# Spectron2.net
KiCad netlist of a schematic drawn in EAGLE
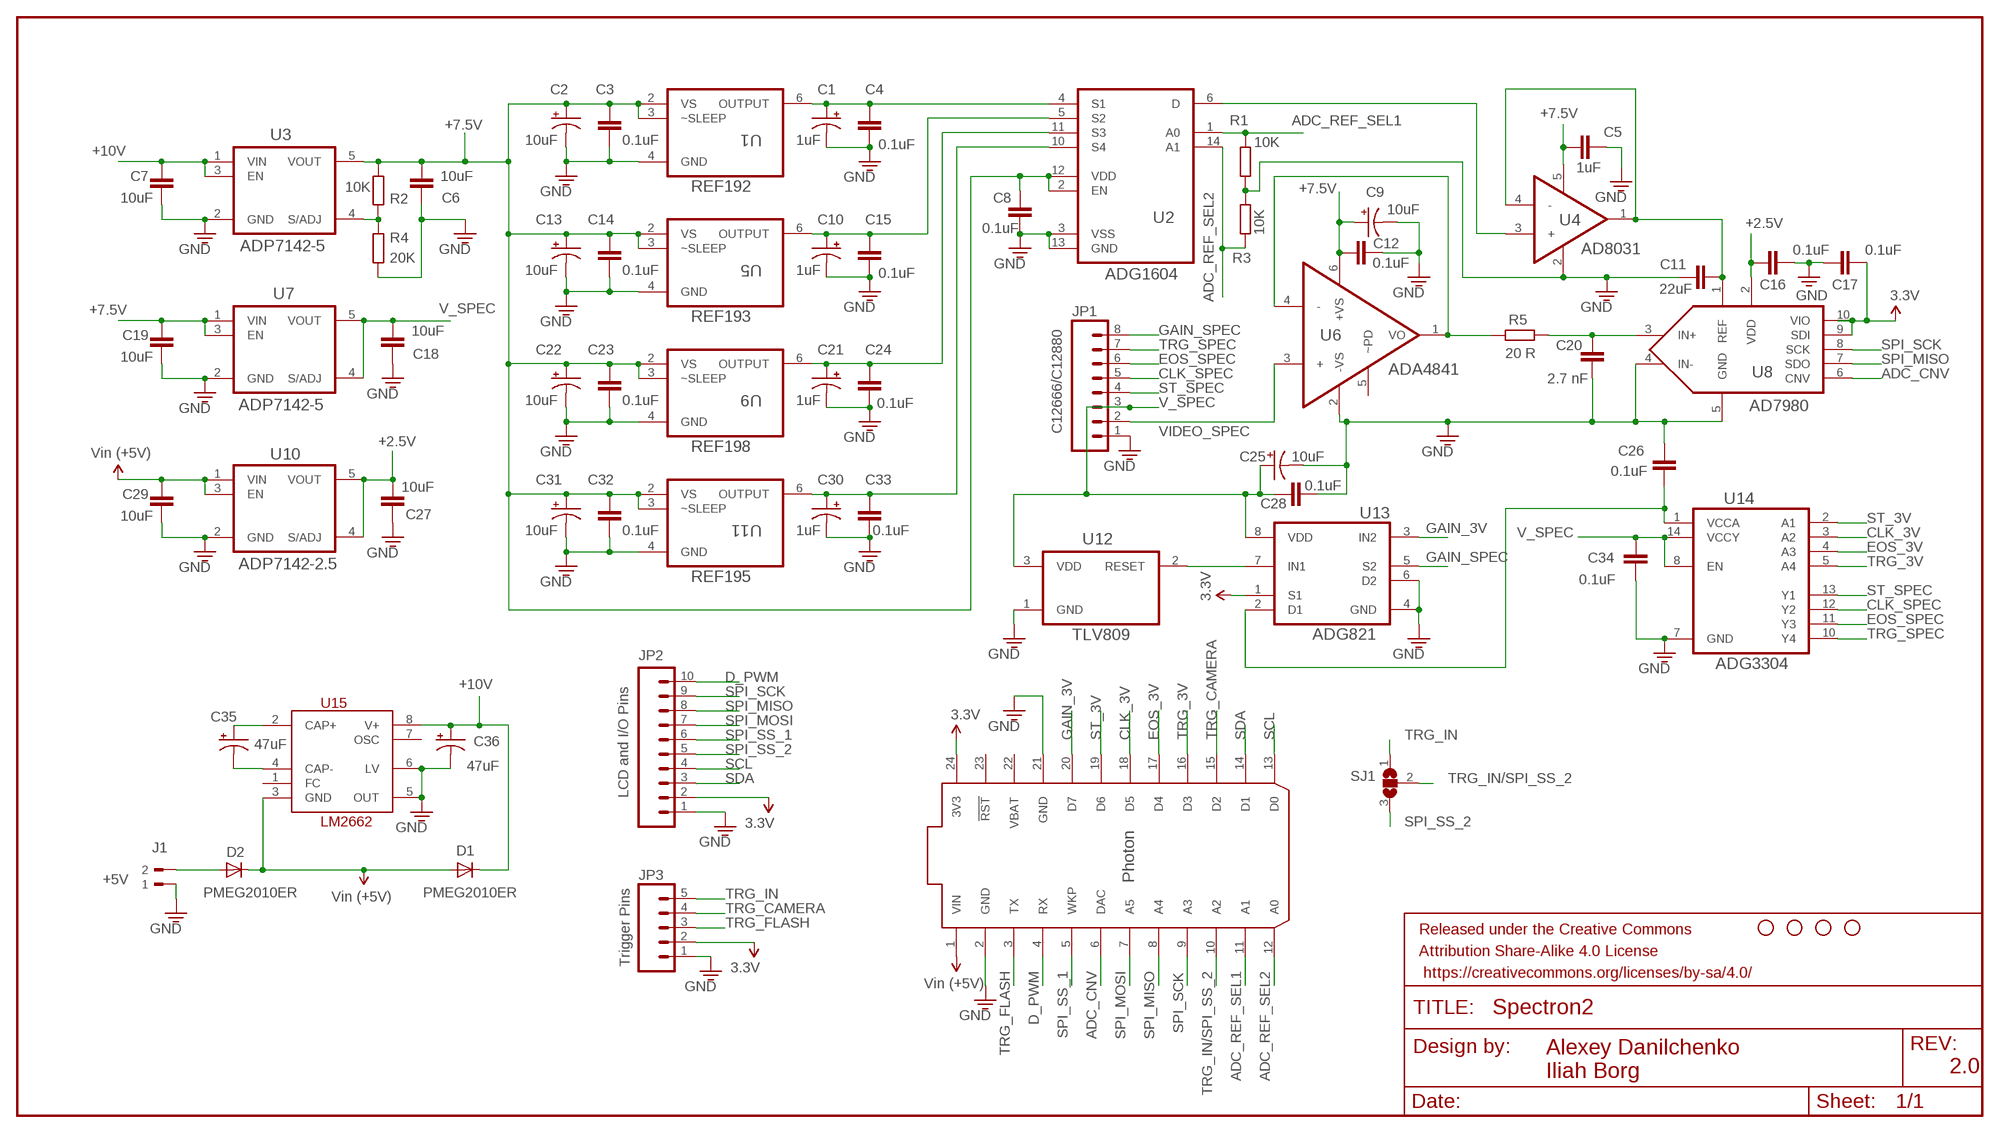
[diagram p0: schematic, sheet 1]

(export (version "E")
  (design (tool "Eeschema 10.0.6"))
  (components
    (comp (ref "C1")
      (value "1uF")
      (footprint "eagle-import:EIA3216")
      (libsource (lib "eagle-import") (part "TANT-CAP1206"))
    )
    (comp (ref "C2")
      (value "10uF")
      (footprint "eagle-import:EIA3216")
      (libsource (lib "eagle-import") (part "Spectron2_TANT-CAP1206"))
    )
    (comp (ref "C3")
      (value "0.1uF")
      (footprint "eagle-import:C0805")
      (libsource (lib "eagle-import") (part "C-EUC0805"))
    )
    (comp (ref "C4")
      (value "0.1uF")
      (footprint "eagle-import:C0805")
      (libsource (lib "eagle-import") (part "C-EUC0805"))
    )
    (comp (ref "C5")
      (value "1uF")
      (footprint "eagle-import:C0805")
      (libsource (lib "eagle-import") (part "C-EUC0805"))
    )
    (comp (ref "C6")
      (value "10uF")
      (footprint "eagle-import:C0805")
      (libsource (lib "eagle-import") (part "C-EUC0805"))
    )
    (comp (ref "C7")
      (value "10uF")
      (footprint "eagle-import:C0805")
      (libsource (lib "eagle-import") (part "C-EUC0805"))
    )
    (comp (ref "C8")
      (value "0.1uF")
      (footprint "eagle-import:C0805")
      (libsource (lib "eagle-import") (part "C-EUC0805"))
    )
    (comp (ref "C9")
      (value "10uF")
      (footprint "eagle-import:EIA3216")
      (libsource (lib "eagle-import") (part "Spectron2_TANT-CAP1206"))
    )
    (comp (ref "C10")
      (value "1uF")
      (footprint "eagle-import:EIA3216")
      (libsource (lib "eagle-import") (part "TANT-CAP1206"))
    )
    (comp (ref "C11")
      (value "22uF")
      (footprint "eagle-import:1206")
      (libsource (lib "eagle-import") (part "CAP1206"))
    )
    (comp (ref "C12")
      (value "0.1uF")
      (footprint "eagle-import:C0805")
      (libsource (lib "eagle-import") (part "C-EUC0805"))
    )
    (comp (ref "C13")
      (value "10uF")
      (footprint "eagle-import:EIA3216")
      (libsource (lib "eagle-import") (part "Spectron2_TANT-CAP1206"))
    )
    (comp (ref "C14")
      (value "0.1uF")
      (footprint "eagle-import:C0805")
      (libsource (lib "eagle-import") (part "C-EUC0805"))
    )
    (comp (ref "C15")
      (value "0.1uF")
      (footprint "eagle-import:C0805")
      (libsource (lib "eagle-import") (part "C-EUC0805"))
    )
    (comp (ref "C16")
      (value "0.1uF")
      (footprint "eagle-import:C0805")
      (libsource (lib "eagle-import") (part "C-EUC0805"))
    )
    (comp (ref "C17")
      (value "0.1uF")
      (footprint "eagle-import:C0805")
      (libsource (lib "eagle-import") (part "C-EUC0805"))
    )
    (comp (ref "C18")
      (value "10uF")
      (footprint "eagle-import:C0805")
      (libsource (lib "eagle-import") (part "C-EUC0805"))
    )
    (comp (ref "C19")
      (value "10uF")
      (footprint "eagle-import:C0805")
      (libsource (lib "eagle-import") (part "C-EUC0805"))
    )
    (comp (ref "C20")
      (value "2.7 nF")
      (footprint "eagle-import:C0805")
      (libsource (lib "eagle-import") (part "C-EUC0805"))
    )
    (comp (ref "C21")
      (value "1uF")
      (footprint "eagle-import:EIA3216")
      (libsource (lib "eagle-import") (part "TANT-CAP1206"))
    )
    (comp (ref "C22")
      (value "10uF")
      (footprint "eagle-import:EIA3216")
      (libsource (lib "eagle-import") (part "Spectron2_TANT-CAP1206"))
    )
    (comp (ref "C23")
      (value "0.1uF")
      (footprint "eagle-import:C0805")
      (libsource (lib "eagle-import") (part "C-EUC0805"))
    )
    (comp (ref "C24")
      (value "0.1uF")
      (footprint "eagle-import:C0805")
      (libsource (lib "eagle-import") (part "C-EUC0805"))
    )
    (comp (ref "C25")
      (value "10uF")
      (footprint "eagle-import:EIA3216")
      (libsource (lib "eagle-import") (part "Spectron2_TANT-CAP1206"))
    )
    (comp (ref "C26")
      (value "0.1uF")
      (footprint "eagle-import:C0805")
      (libsource (lib "eagle-import") (part "C-EUC0805"))
    )
    (comp (ref "C27")
      (value "10uF")
      (footprint "eagle-import:C0805")
      (libsource (lib "eagle-import") (part "C-EUC0805"))
    )
    (comp (ref "C28")
      (value "0.1uF")
      (footprint "eagle-import:C0805")
      (libsource (lib "eagle-import") (part "C-EUC0805"))
    )
    (comp (ref "C29")
      (value "10uF")
      (footprint "eagle-import:C0805")
      (libsource (lib "eagle-import") (part "C-EUC0805"))
    )
    (comp (ref "C30")
      (value "1uF")
      (footprint "eagle-import:EIA3216")
      (libsource (lib "eagle-import") (part "TANT-CAP1206"))
    )
    (comp (ref "C31")
      (value "10uF")
      (footprint "eagle-import:EIA3216")
      (libsource (lib "eagle-import") (part "Spectron2_TANT-CAP1206"))
    )
    (comp (ref "C32")
      (value "0.1uF")
      (footprint "eagle-import:C0805")
      (libsource (lib "eagle-import") (part "C-EUC0805"))
    )
    (comp (ref "C33")
      (value "0.1uF")
      (footprint "eagle-import:C0805")
      (libsource (lib "eagle-import") (part "C-EUC0805"))
    )
    (comp (ref "C34")
      (value "0.1uF")
      (footprint "eagle-import:C0805")
      (libsource (lib "eagle-import") (part "C-EUC0805"))
    )
    (comp (ref "C35")
      (value "47uF")
      (footprint "eagle-import:CT7343")
      (libsource (lib "eagle-import") (part "CPOL-USCT7343"))
    )
    (comp (ref "C36")
      (value "47uF")
      (footprint "eagle-import:CT7343")
      (libsource (lib "eagle-import") (part "CPOL-USCT7343"))
    )
    (comp (ref "D1")
      (value "PMEG2010ER")
      (footprint "eagle-import:SOD123")
      (libsource (lib "eagle-import") (part "DIODE-SOD123"))
    )
    (comp (ref "D2")
      (value "PMEG2010ER")
      (footprint "eagle-import:SOD123")
      (libsource (lib "eagle-import") (part "DIODE-SOD123"))
    )
    (comp (ref "FRAME1")
      (value "FRAME-LEDGER")
      (footprint "eagle-import:CREATIVE_COMMONS")
      (libsource (lib "eagle-import") (part "FRAME-LEDGER"))
    )
    (comp (ref "J1")
      (value "+5V")
      (footprint "eagle-import:WEIDMULLER_PM5.08_2")
      (fields (field (name "MPN") "PM5.08/2/90 BLK"))
      (libsource (lib "eagle-import") (part "PM5.08/2/90BLK"))
    )
    (comp (ref "JP1")
      (value "C12666/C12880")
      (footprint "eagle-import:1X08")
      (libsource (lib "eagle-import") (part "M08SILK_FEMALE_PTH"))
    )
    (comp (ref "JP2")
      (value "LCD and I/O Pins")
      (footprint "eagle-import:1X10")
      (libsource (lib "eagle-import") (part "M10SILK_FEMALE_PTH"))
    )
    (comp (ref "JP3")
      (value "Trigger Pins")
      (footprint "eagle-import:1X05")
      (libsource (lib "eagle-import") (part "M05PTH"))
    )
    (comp (ref "R1")
      (value "10K")
      (footprint "eagle-import:R0805")
      (libsource (lib "eagle-import") (part "R-EU_R0805"))
    )
    (comp (ref "R2")
      (value "10K")
      (footprint "eagle-import:R0805")
      (libsource (lib "eagle-import") (part "R-EU_R0805"))
    )
    (comp (ref "R3")
      (value "10K")
      (footprint "eagle-import:R0805")
      (libsource (lib "eagle-import") (part "R-EU_R0805"))
    )
    (comp (ref "R4")
      (value "20K")
      (footprint "eagle-import:R0805")
      (libsource (lib "eagle-import") (part "R-EU_R0805"))
    )
    (comp (ref "R5")
      (value "20 R")
      (footprint "eagle-import:R0805")
      (libsource (lib "eagle-import") (part "R-EU_R0805"))
    )
    (comp (ref "SJ1")
      (value "SJ2W")
      (footprint "eagle-import:SJ_2")
      (libsource (lib "eagle-import") (part "SJ2W"))
    )
    (comp (ref "STANDOFF1")
      (value "STAND-OFF")
      (footprint "eagle-import:STAND-OFF")
      (libsource (lib "eagle-import") (part "STAND-OFF"))
    )
    (comp (ref "STANDOFF2")
      (value "STAND-OFF")
      (footprint "eagle-import:STAND-OFF")
      (libsource (lib "eagle-import") (part "STAND-OFF"))
    )
    (comp (ref "STANDOFF3")
      (value "STAND-OFF")
      (footprint "eagle-import:STAND-OFF")
      (libsource (lib "eagle-import") (part "STAND-OFF"))
    )
    (comp (ref "STANDOFF4")
      (value "STAND-OFF")
      (footprint "eagle-import:STAND-OFF")
      (libsource (lib "eagle-import") (part "STAND-OFF"))
    )
    (comp (ref "U1")
      (value "REF192")
      (footprint "eagle-import:SOIC127P600X175-8N")
      (libsource (lib "eagle-import") (part "REF192"))
    )
    (comp (ref "U2")
      (value "ADG1604")
      (footprint "eagle-import:SOP65P640X120-14N")
      (fields (field (name "MPN") "ADG1604BRUZ"))
      (libsource (lib "eagle-import") (part "ADG1604"))
    )
    (comp (ref "U3")
      (value "ADP7142-5")
      (footprint "eagle-import:SOT95P280X145-5N")
      (fields (field (name "MPN") "ADP7142"))
      (libsource (lib "eagle-import") (part "ADP7142"))
    )
    (comp (ref "U4")
      (value "AD8031")
      (footprint "eagle-import:SOT95P280X145-5N")
      (libsource (lib "eagle-import") (part "AD8031"))
    )
    (comp (ref "U5")
      (value "REF193")
      (footprint "eagle-import:SOIC127P600X175-8N")
      (libsource (lib "eagle-import") (part "REF193"))
    )
    (comp (ref "U6")
      (value "ADA4841")
      (footprint "eagle-import:SOT95P280X145-6N")
      (fields (field (name "MPN") "ADA4841-1YRJZ-R2"))
      (libsource (lib "eagle-import") (part "ADA4841"))
    )
    (comp (ref "U7")
      (value "ADP7142-5")
      (footprint "eagle-import:SOT95P280X145-5N")
      (fields (field (name "MPN") "ADP7142"))
      (libsource (lib "eagle-import") (part "ADP7142"))
    )
    (comp (ref "U8")
      (value "AD7980")
      (footprint "eagle-import:SOP50P490X110-10N")
      (fields (field (name "MPN") "AD7980ARMZ"))
      (libsource (lib "eagle-import") (part "AD7980"))
    )
    (comp (ref "U9")
      (value "REF198")
      (footprint "eagle-import:SOIC127P600X175-8N")
      (libsource (lib "eagle-import") (part "REF198"))
    )
    (comp (ref "U10")
      (value "ADP7142-2.5")
      (footprint "eagle-import:SOT95P280X145-5N")
      (fields (field (name "MPN") "ADP7142"))
      (libsource (lib "eagle-import") (part "ADP7142"))
    )
    (comp (ref "U11")
      (value "REF195")
      (footprint "eagle-import:SOIC127P600X175-8N")
      (libsource (lib "eagle-import") (part "REF195"))
    )
    (comp (ref "U12")
      (value "TLV809")
      (footprint "eagle-import:SOT95P237X112-3N")
      (fields (field (name "MPN") "TLV80950"))
      (libsource (lib "eagle-import") (part "TLV809"))
    )
    (comp (ref "U13")
      (value "ADG821")
      (footprint "eagle-import:SOP65P490X110-8N")
      (fields (field (name "MPN") "ADG821BRMZ"))
      (libsource (lib "eagle-import") (part "ADG821"))
    )
    (comp (ref "U14")
      (value "ADG3304")
      (footprint "eagle-import:SOP65P640X120-14N")
      (libsource (lib "eagle-import") (part "ADG3304"))
    )
    (comp (ref "U15")
      (value "LM2662")
      (footprint "eagle-import:SOIC8")
      (libsource (lib "eagle-import") (part "LM2662"))
    )
    (comp (ref "U16")
      (value "PHOTON_WITH_HEADERS")
      (footprint "eagle-import:PHOTON")
      (libsource (lib "eagle-import") (part "PHOTON_WITH_HEADERS"))
    )
  )
  (nets
    (net (code "1") (name "/+2.5V") (class "Default")
      (node (ref "C16") (pin "1") (pinfunction "1_1") (pintype "passive"))
      (node (ref "C27") (pin "1") (pinfunction "1_1") (pintype "passive"))
      (node (ref "U10") (pin "4") (pinfunction "S/ADJ_4") (pintype "power_in"))
      (node (ref "U10") (pin "5") (pinfunction "VOUT_5") (pintype "output"))
      (node (ref "U8") (pin "2") (pinfunction "VDD_2") (pintype "power_in"))
    )
    (net (code "2") (name "/+7.5V") (class "Default")
      (node (ref "C12") (pin "2") (pinfunction "2_2") (pintype "passive"))
      (node (ref "C13") (pin "A") (pinfunction "+_A") (pintype "passive"))
      (node (ref "C14") (pin "2") (pinfunction "2_2") (pintype "passive"))
      (node (ref "C19") (pin "2") (pinfunction "2_2") (pintype "passive"))
      (node (ref "C2") (pin "A") (pinfunction "+_A") (pintype "passive"))
      (node (ref "C22") (pin "A") (pinfunction "+_A") (pintype "passive"))
      (node (ref "C23") (pin "2") (pinfunction "2_2") (pintype "passive"))
      (node (ref "C3") (pin "2") (pinfunction "2_2") (pintype "passive"))
      (node (ref "C31") (pin "A") (pinfunction "+_A") (pintype "passive"))
      (node (ref "C32") (pin "2") (pinfunction "2_2") (pintype "passive"))
      (node (ref "C5") (pin "2") (pinfunction "2_2") (pintype "passive"))
      (node (ref "C6") (pin "1") (pinfunction "1_1") (pintype "passive"))
      (node (ref "C8") (pin "2") (pinfunction "2_2") (pintype "passive"))
      (node (ref "C9") (pin "A") (pinfunction "+_A") (pintype "passive"))
      (node (ref "R2") (pin "1") (pinfunction "1_1") (pintype "passive"))
      (node (ref "U1") (pin "2") (pinfunction "VS_2") (pintype "power_in"))
      (node (ref "U1") (pin "3") (pinfunction "~{SLEEP}_3") (pintype "input"))
      (node (ref "U11") (pin "2") (pinfunction "VS_2") (pintype "power_in"))
      (node (ref "U11") (pin "3") (pinfunction "~{SLEEP}_3") (pintype "input"))
      (node (ref "U2") (pin "12") (pinfunction "VDD_12") (pintype "power_in"))
      (node (ref "U2") (pin "2") (pinfunction "EN_2") (pintype "input"))
      (node (ref "U3") (pin "5") (pinfunction "VOUT_5") (pintype "output"))
      (node (ref "U4") (pin "5") (pinfunction "+VS_5") (pintype "power_in"))
      (node (ref "U5") (pin "2") (pinfunction "VS_2") (pintype "power_in"))
      (node (ref "U5") (pin "3") (pinfunction "~{SLEEP}_3") (pintype "input"))
      (node (ref "U6") (pin "6") (pinfunction "+VS_6") (pintype "power_in"))
      (node (ref "U7") (pin "1") (pinfunction "VIN_1") (pintype "input"))
      (node (ref "U7") (pin "3") (pinfunction "EN_3") (pintype "power_in"))
      (node (ref "U9") (pin "2") (pinfunction "VS_2") (pintype "power_in"))
      (node (ref "U9") (pin "3") (pinfunction "~{SLEEP}_3") (pintype "input"))
    )
    (net (code "3") (name "/+10V") (class "Default")
      (node (ref "C36") (pin "+") (pinfunction "+_+") (pintype "passive"))
      (node (ref "C7") (pin "2") (pinfunction "2_2") (pintype "passive"))
      (node (ref "D1") (pin "C") (pinfunction "C_C") (pintype "passive"))
      (node (ref "U15") (pin "8") (pinfunction "V+_8") (pintype "bidirectional"))
      (node (ref "U3") (pin "1") (pinfunction "VIN_1") (pintype "input"))
      (node (ref "U3") (pin "3") (pinfunction "EN_3") (pintype "power_in"))
    )
    (net (code "4") (name "/ADC_CNV") (class "Default")
      (node (ref "U16") (pin "6") (pinfunction "DAC_6") (pintype "bidirectional"))
      (node (ref "U8") (pin "6") (pinfunction "CNV_6") (pintype "input"))
    )
    (net (code "5") (name "/ADC_REF_SEL1") (class "Default")
      (node (ref "R1") (pin "1") (pinfunction "1_1") (pintype "passive"))
      (node (ref "U16") (pin "11") (pinfunction "A1_11") (pintype "bidirectional"))
      (node (ref "U2") (pin "1") (pinfunction "A0_1") (pintype "input"))
    )
    (net (code "6") (name "/ADC_REF_SEL2") (class "Default")
      (node (ref "R3") (pin "2") (pinfunction "2_2") (pintype "passive"))
      (node (ref "U16") (pin "12") (pinfunction "A0_12") (pintype "bidirectional"))
      (node (ref "U2") (pin "14") (pinfunction "A1_14") (pintype "input"))
    )
    (net (code "7") (name "/CLK_3V") (class "Default")
      (node (ref "U14") (pin "3") (pinfunction "A2_3") (pintype "bidirectional"))
      (node (ref "U16") (pin "18") (pinfunction "D5_18") (pintype "bidirectional"))
    )
    (net (code "8") (name "/CLK_SPEC") (class "Default")
      (node (ref "JP1") (pin "5") (pinfunction "5_5") (pintype "passive"))
      (node (ref "U14") (pin "12") (pinfunction "Y2_12") (pintype "bidirectional"))
    )
    (net (code "9") (name "/D_PWM") (class "Default")
      (node (ref "JP2") (pin "10") (pinfunction "10_10") (pintype "passive"))
      (node (ref "U16") (pin "4") (pinfunction "RX_4") (pintype "bidirectional"))
    )
    (net (code "10") (name "/EOS_3V") (class "Default")
      (node (ref "U14") (pin "4") (pinfunction "A3_4") (pintype "bidirectional"))
      (node (ref "U16") (pin "17") (pinfunction "D4_17") (pintype "bidirectional"))
    )
    (net (code "11") (name "/EOS_SPEC") (class "Default")
      (node (ref "JP1") (pin "6") (pinfunction "6_6") (pintype "passive"))
      (node (ref "U14") (pin "11") (pinfunction "Y3_11") (pintype "bidirectional"))
    )
    (net (code "12") (name "/GAIN_3V") (class "Default")
      (node (ref "U13") (pin "3") (pinfunction "IN2_3") (pintype "input"))
      (node (ref "U16") (pin "20") (pinfunction "D7_20") (pintype "bidirectional"))
    )
    (net (code "13") (name "/GAIN_SPEC") (class "Default")
      (node (ref "JP1") (pin "8") (pinfunction "8_8") (pintype "passive"))
      (node (ref "U13") (pin "5") (pinfunction "S2_5") (pintype "bidirectional"))
    )
    (net (code "14") (name "/SCL") (class "Default")
      (node (ref "JP2") (pin "4") (pinfunction "4_4") (pintype "passive"))
      (node (ref "U16") (pin "13") (pinfunction "D0_13") (pintype "bidirectional"))
    )
    (net (code "15") (name "/SDA") (class "Default")
      (node (ref "JP2") (pin "3") (pinfunction "3_3") (pintype "passive"))
      (node (ref "U16") (pin "14") (pinfunction "D1_14") (pintype "bidirectional"))
    )
    (net (code "16") (name "/SPI_MISO") (class "Default")
      (node (ref "JP2") (pin "8") (pinfunction "8_8") (pintype "passive"))
      (node (ref "U16") (pin "8") (pinfunction "A4_8") (pintype "bidirectional"))
      (node (ref "U8") (pin "7") (pinfunction "SDO_7") (pintype "output"))
    )
    (net (code "17") (name "/SPI_MOSI") (class "Default")
      (node (ref "JP2") (pin "7") (pinfunction "7_7") (pintype "passive"))
      (node (ref "U16") (pin "7") (pinfunction "A5_7") (pintype "bidirectional"))
    )
    (net (code "18") (name "/SPI_SCK") (class "Default")
      (node (ref "JP2") (pin "9") (pinfunction "9_9") (pintype "passive"))
      (node (ref "U16") (pin "9") (pinfunction "A3_9") (pintype "bidirectional"))
      (node (ref "U8") (pin "8") (pinfunction "SCK_8") (pintype "input"))
    )
    (net (code "19") (name "/SPI_SS_1") (class "Default")
      (node (ref "JP2") (pin "6") (pinfunction "6_6") (pintype "passive"))
      (node (ref "U16") (pin "5") (pinfunction "WKP_5") (pintype "bidirectional"))
    )
    (net (code "20") (name "/SPI_SS_2") (class "Default")
      (node (ref "JP2") (pin "5") (pinfunction "5_5") (pintype "passive"))
      (node (ref "SJ1") (pin "3") (pinfunction "3_3") (pintype "passive"))
    )
    (net (code "21") (name "/ST_3V") (class "Default")
      (node (ref "U14") (pin "2") (pinfunction "A1_2") (pintype "bidirectional"))
      (node (ref "U16") (pin "19") (pinfunction "D6_19") (pintype "bidirectional"))
    )
    (net (code "22") (name "/ST_SPEC") (class "Default")
      (node (ref "JP1") (pin "4") (pinfunction "4_4") (pintype "passive"))
      (node (ref "U14") (pin "13") (pinfunction "Y1_13") (pintype "bidirectional"))
    )
    (net (code "23") (name "/TRG_3V") (class "Default")
      (node (ref "U14") (pin "5") (pinfunction "A4_5") (pintype "bidirectional"))
      (node (ref "U16") (pin "16") (pinfunction "D3_16") (pintype "bidirectional"))
    )
    (net (code "24") (name "/TRG_CAMERA") (class "Default")
      (node (ref "JP3") (pin "4") (pinfunction "4_4") (pintype "passive"))
      (node (ref "U16") (pin "15") (pinfunction "D2_15") (pintype "bidirectional"))
    )
    (net (code "25") (name "/TRG_FLASH") (class "Default")
      (node (ref "JP3") (pin "3") (pinfunction "3_3") (pintype "passive"))
      (node (ref "U16") (pin "3") (pinfunction "TX_3") (pintype "bidirectional"))
    )
    (net (code "26") (name "/TRG_IN") (class "Default")
      (node (ref "JP3") (pin "5") (pinfunction "5_5") (pintype "passive"))
      (node (ref "SJ1") (pin "1") (pinfunction "1_1") (pintype "passive"))
    )
    (net (code "27") (name "/TRG_IN{slash}SPI_SS_2") (class "Default")
      (node (ref "SJ1") (pin "2") (pinfunction "2_2") (pintype "passive"))
      (node (ref "U16") (pin "10") (pinfunction "A2_10") (pintype "bidirectional"))
    )
    (net (code "28") (name "/TRG_SPEC") (class "Default")
      (node (ref "JP1") (pin "7") (pinfunction "7_7") (pintype "passive"))
      (node (ref "U14") (pin "10") (pinfunction "Y4_10") (pintype "bidirectional"))
    )
    (net (code "29") (name "/VBAT") (class "Default")
      (node (ref "U16") (pin "22") (pinfunction "VBAT_22") (pintype "power_in"))
    )
    (net (code "30") (name "/VIDEO_SPEC") (class "Default")
      (node (ref "JP1") (pin "2") (pinfunction "2_2") (pintype "passive"))
      (node (ref "U6") (pin "3") (pinfunction "+_3") (pintype "input"))
    )
    (net (code "31") (name "/V_SPEC") (class "Default")
      (node (ref "C18") (pin "1") (pinfunction "1_1") (pintype "passive"))
      (node (ref "C25") (pin "A") (pinfunction "+_A") (pintype "passive"))
      (node (ref "C28") (pin "2") (pinfunction "2_2") (pintype "passive"))
      (node (ref "C34") (pin "2") (pinfunction "2_2") (pintype "passive"))
      (node (ref "JP1") (pin "3") (pinfunction "3_3") (pintype "passive"))
      (node (ref "U12") (pin "3") (pinfunction "VDD_3") (pintype "power_in"))
      (node (ref "U13") (pin "8") (pinfunction "VDD_8") (pintype "power_in"))
      (node (ref "U14") (pin "14") (pinfunction "VCCY_14") (pintype "power_in"))
      (node (ref "U14") (pin "8") (pinfunction "EN_8") (pintype "input"))
      (node (ref "U7") (pin "4") (pinfunction "S/ADJ_4") (pintype "power_in"))
      (node (ref "U7") (pin "5") (pinfunction "VOUT_5") (pintype "output"))
    )
    (net (code "32") (name "3.3V") (class "Default")
      (node (ref "C17") (pin "2") (pinfunction "2_2") (pintype "passive"))
      (node (ref "JP2") (pin "2") (pinfunction "2_2") (pintype "passive"))
      (node (ref "JP3") (pin "2") (pinfunction "2_2") (pintype "passive"))
      (node (ref "U13") (pin "1") (pinfunction "S1_1") (pintype "bidirectional"))
      (node (ref "U16") (pin "24") (pinfunction "3V3_24") (pintype "power_in"))
      (node (ref "U8") (pin "10") (pinfunction "VIO_10") (pintype "power_in"))
      (node (ref "U8") (pin "9") (pinfunction "SDI_9") (pintype "input"))
    )
    (net (code "33") (name "GND") (class "Default")
      (node (ref "C1") (pin "C") (pinfunction "-_C") (pintype "passive"))
      (node (ref "C10") (pin "C") (pinfunction "-_C") (pintype "passive"))
      (node (ref "C11") (pin "1") (pinfunction "1_1") (pintype "passive"))
      (node (ref "C12") (pin "1") (pinfunction "1_1") (pintype "passive"))
      (node (ref "C13") (pin "C") (pinfunction "-_C") (pintype "passive"))
      (node (ref "C14") (pin "1") (pinfunction "1_1") (pintype "passive"))
      (node (ref "C15") (pin "1") (pinfunction "1_1") (pintype "passive"))
      (node (ref "C16") (pin "2") (pinfunction "2_2") (pintype "passive"))
      (node (ref "C17") (pin "1") (pinfunction "1_1") (pintype "passive"))
      (node (ref "C18") (pin "2") (pinfunction "2_2") (pintype "passive"))
      (node (ref "C19") (pin "1") (pinfunction "1_1") (pintype "passive"))
      (node (ref "C2") (pin "C") (pinfunction "-_C") (pintype "passive"))
      (node (ref "C20") (pin "1") (pinfunction "1_1") (pintype "passive"))
      (node (ref "C21") (pin "C") (pinfunction "-_C") (pintype "passive"))
      (node (ref "C22") (pin "C") (pinfunction "-_C") (pintype "passive"))
      (node (ref "C23") (pin "1") (pinfunction "1_1") (pintype "passive"))
      (node (ref "C24") (pin "1") (pinfunction "1_1") (pintype "passive"))
      (node (ref "C25") (pin "C") (pinfunction "-_C") (pintype "passive"))
      (node (ref "C26") (pin "2") (pinfunction "2_2") (pintype "passive"))
      (node (ref "C27") (pin "2") (pinfunction "2_2") (pintype "passive"))
      (node (ref "C28") (pin "1") (pinfunction "1_1") (pintype "passive"))
      (node (ref "C29") (pin "1") (pinfunction "1_1") (pintype "passive"))
      (node (ref "C3") (pin "1") (pinfunction "1_1") (pintype "passive"))
      (node (ref "C30") (pin "C") (pinfunction "-_C") (pintype "passive"))
      (node (ref "C31") (pin "C") (pinfunction "-_C") (pintype "passive"))
      (node (ref "C32") (pin "1") (pinfunction "1_1") (pintype "passive"))
      (node (ref "C33") (pin "1") (pinfunction "1_1") (pintype "passive"))
      (node (ref "C34") (pin "1") (pinfunction "1_1") (pintype "passive"))
      (node (ref "C36") (pin "-") (pinfunction "-_-") (pintype "passive"))
      (node (ref "C4") (pin "1") (pinfunction "1_1") (pintype "passive"))
      (node (ref "C5") (pin "1") (pinfunction "1_1") (pintype "passive"))
      (node (ref "C6") (pin "2") (pinfunction "2_2") (pintype "passive"))
      (node (ref "C7") (pin "1") (pinfunction "1_1") (pintype "passive"))
      (node (ref "C8") (pin "1") (pinfunction "1_1") (pintype "passive"))
      (node (ref "C9") (pin "C") (pinfunction "-_C") (pintype "passive"))
      (node (ref "J1") (pin "1") (pinfunction "1_1") (pintype "passive"))
      (node (ref "JP1") (pin "1") (pinfunction "1_1") (pintype "passive"))
      (node (ref "JP2") (pin "1") (pinfunction "1_1") (pintype "passive"))
      (node (ref "JP3") (pin "1") (pinfunction "1_1") (pintype "passive"))
      (node (ref "R1") (pin "2") (pinfunction "2_2") (pintype "passive"))
      (node (ref "R3") (pin "1") (pinfunction "1_1") (pintype "passive"))
      (node (ref "R4") (pin "2") (pinfunction "2_2") (pintype "passive"))
      (node (ref "U1") (pin "4") (pinfunction "GND_4") (pintype "passive"))
      (node (ref "U10") (pin "2") (pinfunction "GND_2") (pintype "input"))
      (node (ref "U11") (pin "4") (pinfunction "GND_4") (pintype "passive"))
      (node (ref "U12") (pin "1") (pinfunction "GND_1") (pintype "passive"))
      (node (ref "U13") (pin "4") (pinfunction "GND_4") (pintype "passive"))
      (node (ref "U13") (pin "6") (pinfunction "D2_6") (pintype "bidirectional"))
      (node (ref "U14") (pin "7") (pinfunction "GND_7") (pintype "power_in"))
      (node (ref "U15") (pin "5") (pinfunction "OUT_5") (pintype "bidirectional"))
      (node (ref "U15") (pin "6") (pinfunction "LV_6") (pintype "bidirectional"))
      (node (ref "U16") (pin "2") (pinfunction "GND_2") (pintype "power_in"))
      (node (ref "U16") (pin "21") (pinfunction "GND_21") (pintype "power_in"))
      (node (ref "U2") (pin "13") (pinfunction "GND_13") (pintype "passive"))
      (node (ref "U2") (pin "3") (pinfunction "VSS_3") (pintype "power_in"))
      (node (ref "U3") (pin "2") (pinfunction "GND_2") (pintype "input"))
      (node (ref "U4") (pin "2") (pinfunction "-VS_2") (pintype "power_in"))
      (node (ref "U5") (pin "4") (pinfunction "GND_4") (pintype "passive"))
      (node (ref "U6") (pin "2") (pinfunction "-VS_2") (pintype "power_in"))
      (node (ref "U7") (pin "2") (pinfunction "GND_2") (pintype "input"))
      (node (ref "U8") (pin "4") (pinfunction "IN-_4") (pintype "input"))
      (node (ref "U8") (pin "5") (pinfunction "GND_5") (pintype "passive"))
      (node (ref "U9") (pin "4") (pinfunction "GND_4") (pintype "passive"))
    )
    (net (code "34") (name "Net-(C1-+)") (class "Default")
      (node (ref "C1") (pin "A") (pinfunction "+_A") (pintype "passive"))
      (node (ref "C4") (pin "2") (pinfunction "2_2") (pintype "passive"))
      (node (ref "U1") (pin "6") (pinfunction "OUTPUT_6") (pintype "output"))
      (node (ref "U2") (pin "4") (pinfunction "S1_4") (pintype "bidirectional"))
    )
    (net (code "35") (name "Net-(C10-+)") (class "Default")
      (node (ref "C10") (pin "A") (pinfunction "+_A") (pintype "passive"))
      (node (ref "C15") (pin "2") (pinfunction "2_2") (pintype "passive"))
      (node (ref "U2") (pin "5") (pinfunction "S2_5") (pintype "bidirectional"))
      (node (ref "U5") (pin "6") (pinfunction "OUTPUT_6") (pintype "output"))
    )
    (net (code "36") (name "Net-(C21-+)") (class "Default")
      (node (ref "C21") (pin "A") (pinfunction "+_A") (pintype "passive"))
      (node (ref "C24") (pin "2") (pinfunction "2_2") (pintype "passive"))
      (node (ref "U2") (pin "11") (pinfunction "S3_11") (pintype "bidirectional"))
      (node (ref "U9") (pin "6") (pinfunction "OUTPUT_6") (pintype "output"))
    )
    (net (code "37") (name "Net-(C30-+)") (class "Default")
      (node (ref "C30") (pin "A") (pinfunction "+_A") (pintype "passive"))
      (node (ref "C33") (pin "2") (pinfunction "2_2") (pintype "passive"))
      (node (ref "U11") (pin "6") (pinfunction "OUTPUT_6") (pintype "output"))
      (node (ref "U2") (pin "10") (pinfunction "S4_10") (pintype "bidirectional"))
    )
    (net (code "38") (name "Net-(D2-PadA)") (class "Default")
      (node (ref "D2") (pin "A") (pinfunction "A_A") (pintype "passive"))
      (node (ref "J1") (pin "2") (pinfunction "2_2") (pintype "passive"))
    )
    (net (code "39") (name "Net-(U2-D)") (class "Default")
      (node (ref "U2") (pin "6") (pinfunction "D_6") (pintype "bidirectional"))
      (node (ref "U4") (pin "3") (pinfunction "+_3") (pintype "input"))
    )
    (net (code "40") (name "Net-(U3-S{slash}ADJ)") (class "Default")
      (node (ref "R2") (pin "2") (pinfunction "2_2") (pintype "passive"))
      (node (ref "R4") (pin "1") (pinfunction "1_1") (pintype "passive"))
      (node (ref "U3") (pin "4") (pinfunction "S/ADJ_4") (pintype "power_in"))
    )
    (net (code "41") (name "Net-(U4--)") (class "Default")
      (node (ref "C11") (pin "2") (pinfunction "2_2") (pintype "passive"))
      (node (ref "U4") (pin "1") (pinfunction "VOUT_1") (pintype "output"))
      (node (ref "U4") (pin "4") (pinfunction "-_4") (pintype "input"))
      (node (ref "U8") (pin "1") (pinfunction "REF_1") (pintype "input"))
    )
    (net (code "42") (name "Net-(U6--)") (class "Default")
      (node (ref "R5") (pin "2") (pinfunction "2_2") (pintype "passive"))
      (node (ref "U6") (pin "1") (pinfunction "VO_1") (pintype "output"))
      (node (ref "U6") (pin "4") (pinfunction "-_4") (pintype "input"))
    )
    (net (code "43") (name "Net-(U8-IN+)") (class "Default")
      (node (ref "C20") (pin "2") (pinfunction "2_2") (pintype "passive"))
      (node (ref "R5") (pin "1") (pinfunction "1_1") (pintype "passive"))
      (node (ref "U8") (pin "3") (pinfunction "IN+_3") (pintype "input"))
    )
    (net (code "44") (name "Net-(U12-RESET)") (class "Default")
      (node (ref "U12") (pin "2") (pinfunction "RESET_2") (pintype "output"))
      (node (ref "U13") (pin "7") (pinfunction "IN1_7") (pintype "input"))
    )
    (net (code "45") (name "Net-(U13-D1)") (class "Default")
      (node (ref "C26") (pin "1") (pinfunction "1_1") (pintype "passive"))
      (node (ref "U13") (pin "2") (pinfunction "D1_2") (pintype "bidirectional"))
      (node (ref "U14") (pin "1") (pinfunction "VCCA_1") (pintype "power_in"))
    )
    (net (code "46") (name "Net-(U15-CAP+)") (class "Default")
      (node (ref "C35") (pin "+") (pinfunction "+_+") (pintype "passive"))
      (node (ref "U15") (pin "2") (pinfunction "CAP+_2") (pintype "bidirectional"))
    )
    (net (code "47") (name "Net-(U15-CAP-)") (class "Default")
      (node (ref "C35") (pin "-") (pinfunction "-_-") (pintype "passive"))
      (node (ref "U15") (pin "4") (pinfunction "CAP-_4") (pintype "bidirectional"))
    )
    (net (code "48") (name "VIN") (class "Default")
      (node (ref "C29") (pin "2") (pinfunction "2_2") (pintype "passive"))
      (node (ref "D1") (pin "A") (pinfunction "A_A") (pintype "passive"))
      (node (ref "D2") (pin "C") (pinfunction "C_C") (pintype "passive"))
      (node (ref "U10") (pin "1") (pinfunction "VIN_1") (pintype "input"))
      (node (ref "U10") (pin "3") (pinfunction "EN_3") (pintype "power_in"))
      (node (ref "U15") (pin "3") (pinfunction "GND_3") (pintype "bidirectional"))
      (node (ref "U16") (pin "1") (pinfunction "VIN_1") (pintype "power_in"))
    )
    (net (code "49") (name "unconnected-(U6-~{PD}-Pad5)") (class "Default")
      (node (ref "U6") (pin "5") (pinfunction "~{PD}_5") (pintype "input"))
    )
    (net (code "50") (name "unconnected-(U15-FC-Pad1)") (class "Default")
      (node (ref "U15") (pin "1") (pinfunction "FC_1") (pintype "bidirectional"))
    )
    (net (code "51") (name "unconnected-(U15-OSC-Pad7)") (class "Default")
      (node (ref "U15") (pin "7") (pinfunction "OSC_7") (pintype "bidirectional"))
    )
    (net (code "52") (name "unconnected-(U16-~{RST}-Pad23)") (class "Default")
      (node (ref "U16") (pin "23") (pinfunction "~{RST}_23") (pintype "bidirectional"))
    )
  )
)
